# cc2520_cc2592.net
KiCad netlist of a schematic drawn in Altium Designer
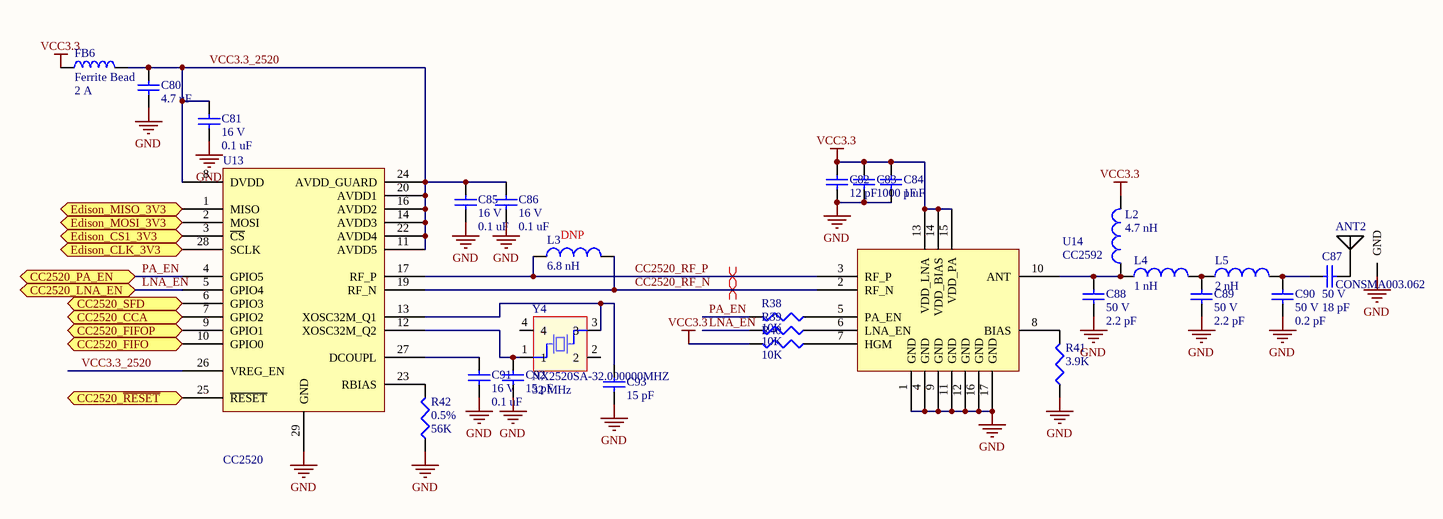
[diagram p0: cc2520_cc2592.SchDoc]

(export (version "E")
  (design (tool "Eeschema 10.0.6"))
  (components
    (comp (ref "ANT2")
      (value "CONSMA003.062")
      (footprint "CONSMA003.062")
      (description "CONN SMA JACK 50 OHM EDGE MNT")
      (libsource (lib "RF") (part "CONSMA003.062"))
    )
    (comp (ref "C80")
      (value "4.7 uF")
      (footprint "0603")
      (description "Ceramic capacitor, 4.7u, 10V, 0603 package")
      (fields (field (name "TOLERANCE") "20%") (field (name "Comment") "Ceramic capacitor"))
      (libsource (lib "rlc") (part "C_4.7u_10V_0603_ceramic"))
    )
    (comp (ref "C81")
      (value "0.1 uF")
      (footprint "0402")
      (description "Ceramic capacitor, 0.1u, 16 V, 0402 package")
      (fields
        (field (name "TOLERANCE") "10%")
        (field (name "VOLTAGE RATED") "16 V")
        (field (name "Comment") "Ceramic capacitor")
      )
      (libsource (lib "rlc") (part "C_0.1u_16V_0402_ceramic"))
    )
    (comp (ref "C82")
      (value "12 pF")
      (footprint "0402")
      (description "Ceramic capacitor, 12 pF, 0402 package")
      (fields (field (name "TOLERANCE") "2%") (field (name "Comment") "Ceramic capacitor"))
      (libsource (lib "rlc") (part "C_12p_0402_ceramic"))
    )
    (comp (ref "C83")
      (value "1000 pF")
      (footprint "0402")
      (description "Ceramic capacitor, 1000 pF, 0402 package")
      (fields (field (name "TOLERANCE") "10%") (field (name "Comment") "Ceramic capacitor"))
      (libsource (lib "rlc") (part "C_1000p_50V_0402_ceramic"))
    )
    (comp (ref "C84")
      (value "1 uF")
      (footprint "0402")
      (description "Ceramic capacitor, 1 uF, 16V, 0402 package")
      (fields (field (name "TOLERANCE") "10%") (field (name "Comment") "Ceramic capacitor"))
      (libsource (lib "rlc") (part "C_1u_16V_0402_ceramic"))
    )
    (comp (ref "C85")
      (value "0.1 uF")
      (footprint "0402")
      (description "Ceramic capacitor, 0.1u, 16 V, 0402 package")
      (fields
        (field (name "TOLERANCE") "10%")
        (field (name "VOLTAGE RATED") "16 V")
        (field (name "Comment") "Ceramic capacitor")
      )
      (libsource (lib "rlc") (part "C_0.1u_16V_0402_ceramic"))
    )
    (comp (ref "C86")
      (value "0.1 uF")
      (footprint "0402")
      (description "Ceramic capacitor, 0.1u, 16 V, 0402 package")
      (fields
        (field (name "TOLERANCE") "10%")
        (field (name "VOLTAGE RATED") "16 V")
        (field (name "Comment") "Ceramic capacitor")
      )
      (libsource (lib "rlc") (part "C_0.1u_16V_0402_ceramic"))
    )
    (comp (ref "C87")
      (value "18 pF")
      (footprint "0402")
      (description "Ceramic capacitor, 18 pF, 0402 package")
      (fields
        (field (name "TOLERANCE") "2%")
        (field (name "VOLTAGE RATED") "50 V")
        (field (name "Comment") "Ceramic capacitor")
      )
      (libsource (lib "rlc") (part "C_18p_50V_0402_ceramic"))
    )
    (comp (ref "C88")
      (value "2.2 pF")
      (footprint "0402")
      (description "Ceramic capacitor, 2.2 pF, 0402 package")
      (fields
        (field (name "TOLERANCE") "0.1 pF")
        (field (name "VOLTAGE RATED") "50 V")
        (field (name "Comment") "Ceramic capacitor")
      )
      (libsource (lib "rlc") (part "C_2.2p_50V_0402_ceramic"))
    )
    (comp (ref "C89")
      (value "2.2 pF")
      (footprint "0402")
      (description "Ceramic capacitor, 2.2 pF, 0402 package")
      (fields
        (field (name "TOLERANCE") "0.1 pF")
        (field (name "VOLTAGE RATED") "50 V")
        (field (name "Comment") "Ceramic capacitor")
      )
      (libsource (lib "rlc") (part "C_2.2p_50V_0402_ceramic"))
    )
    (comp (ref "C90")
      (value "0.2 pF")
      (footprint "0402")
      (description "Ceramic capacitor, 0.2 pF, 0402 package")
      (fields
        (field (name "TOLERANCE") "0.05 pF")
        (field (name "VOLTAGE RATED") "50 V")
        (field (name "Comment") "Ceramic capacitor")
      )
      (libsource (lib "rlc") (part "C_0.2p_50V_0402_ceramic"))
    )
    (comp (ref "C91")
      (value "0.1 uF")
      (footprint "0402")
      (description "Ceramic capacitor, 0.1u, 16 V, 0402 package")
      (fields
        (field (name "TOLERANCE") "10%")
        (field (name "VOLTAGE RATED") "16 V")
        (field (name "Comment") "Ceramic capacitor")
      )
      (libsource (lib "rlc") (part "C_0.1u_16V_0402_ceramic"))
    )
    (comp (ref "C92")
      (value "15 pF")
      (footprint "0402")
      (description "Ceramic capacitor, 15 pF, 25V, 0402 package")
      (fields (field (name "TOLERANCE") "5%") (field (name "Comment") "Ceramic capacitor"))
      (libsource (lib "rlc") (part "C_15p_25V_0402_ceramic"))
    )
    (comp (ref "C93")
      (value "15 pF")
      (footprint "0402")
      (description "Ceramic capacitor, 15 pF, 25V, 0402 package")
      (fields (field (name "TOLERANCE") "5%") (field (name "Comment") "Ceramic capacitor"))
      (libsource (lib "rlc") (part "C_15p_25V_0402_ceramic"))
    )
    (comp (ref "FB6")
      (value "Ferrite Bead")
      (footprint "0603")
      (description "Ferrite Bead, 2 A, 0603 package")
      (fields (field (name "CURRENT RATING") "2 A"))
      (libsource (lib "rlc") (part "FB_2A_0603"))
    )
    (comp (ref "L2")
      (value "4.7 nH")
      (footprint "0402")
      (description "Chip inductor, 4.7 nH, 0402 package, 300 mA")
      (fields (field (name "TOLERANCE") "0.3 nH") (field (name "Comment") "Chip inductor"))
      (libsource (lib "rlc") (part "L_4.7n_300mA_0402"))
    )
    (comp (ref "L3")
      (value "6.8 nH")
      (footprint "0402")
      (description "Chip inductor, 6.8 nH, 0402 package")
      (fields (field (name "TOLERANCE") "5%") (field (name "Comment") "Chip inductor"))
      (libsource (lib "rlc") (part "L_6.8n_0402"))
    )
    (comp (ref "L4")
      (value "1 nH")
      (footprint "0402")
      (description "Chip inductor, 1 nH, 0402 package, 300 mA")
      (fields (field (name "TOLERANCE") "0.3 nH") (field (name "Comment") "Chip inductor"))
      (libsource (lib "rlc") (part "L_1n_300mA_0402"))
    )
    (comp (ref "L5")
      (value "2 nH")
      (footprint "0402")
      (description "Chip inductor, 2 nH, 0402 package, 300 mA")
      (fields (field (name "TOLERANCE") "0.3 nH") (field (name "Comment") "Chip inductor"))
      (libsource (lib "rlc") (part "L_2n_300mA_0402"))
    )
    (comp (ref "R38")
      (value "10K")
      (footprint "0402")
      (description "Chip resistor, 10K, 0402 package")
      (fields (field (name "TOLERANCE") "1%") (field (name "POWER") "1/16 W"))
      (libsource (lib "rlc") (part "R_10K_0402"))
    )
    (comp (ref "R39")
      (value "10K")
      (footprint "0402")
      (description "Chip resistor, 10K, 0402 package")
      (fields (field (name "TOLERANCE") "1%") (field (name "POWER") "1/16 W"))
      (libsource (lib "rlc") (part "R_10K_0402"))
    )
    (comp (ref "R40")
      (value "10K")
      (footprint "0402")
      (description "Chip resistor, 10K, 0402 package")
      (fields (field (name "TOLERANCE") "1%") (field (name "POWER") "1/16 W"))
      (libsource (lib "rlc") (part "R_10K_0402"))
    )
    (comp (ref "R41")
      (value "3.9K")
      (footprint "0402")
      (description "Chip resistor, 3.9K, 0402 package")
      (fields (field (name "TOLERANCE") "1%") (field (name "POWER") "1/16 W"))
      (libsource (lib "rlc") (part "R_3.9K_0402"))
    )
    (comp (ref "R42")
      (value "56K")
      (footprint "0402")
      (description "Chip resistor, 56K, 0402 package")
      (fields
        (field (name "POWER") "1/16 W")
        (field (name "TOLERANCE") "0.5%")
        (field (name "Comment") "Chip resistor")
      )
      (libsource (lib "rlc") (part "R_56K_0402"))
    )
    (comp (ref "U13")
      (value "CC2520")
      (footprint "QFN-28")
      (description "2.4 GHZ IEEE 802.15.4/ZIGBEE® RF TRANSCEIVER")
      (libsource (lib "RF") (part "CC2520"))
    )
    (comp (ref "U14")
      (value "CC2592")
      (footprint "QFN-16")
      (description "2.4-GHz Range Extender")
      (libsource (lib "RF") (part "CC2592"))
    )
    (comp (ref "Y4")
      (value "NX2520SA-32.000000MHZ")
      (footprint "NX2520SA")
      (description "Crystal 32.0000MHz 10ppm 10pF 50 Ohm")
      (fields (field (name "FREQUENCY") "32 MHz"))
      (libsource (lib "crystal_oscillators_rtc") (part "NX2520SA-32.000000MHZ"))
    )
  )
  (nets
    (net (code "1") (name "/CC2520_CCA") (class "Default")
      (node (ref "U13") (pin "7") (pinfunction "GPIO2_7") (pintype "passive"))
    )
    (net (code "2") (name "/CC2520_FIFO") (class "Default")
      (node (ref "U13") (pin "10") (pinfunction "GPIO0_10") (pintype "passive"))
    )
    (net (code "3") (name "/CC2520_FIFOP") (class "Default")
      (node (ref "U13") (pin "9") (pinfunction "GPIO1_9") (pintype "passive"))
    )
    (net (code "4") (name "/CC2520_RF_N") (class "Default")
      (node (ref "L3") (pin "1") (pintype "passive"))
      (node (ref "U13") (pin "19") (pinfunction "RF_N_19") (pintype "passive"))
      (node (ref "U14") (pin "2") (pinfunction "RF_N_2") (pintype "passive"))
    )
    (net (code "5") (name "/CC2520_RF_P") (class "Default")
      (node (ref "L3") (pin "2") (pintype "passive"))
      (node (ref "U13") (pin "17") (pinfunction "RF_P_17") (pintype "passive"))
      (node (ref "U14") (pin "3") (pinfunction "RF_P_3") (pintype "passive"))
    )
    (net (code "6") (name "/CC2520_SFD") (class "Default")
      (node (ref "U13") (pin "6") (pinfunction "GPIO3_6") (pintype "passive"))
    )
    (net (code "7") (name "/CC2520_~{RESET}") (class "Default")
      (node (ref "U13") (pin "25") (pinfunction "~{RESET}_25") (pintype "passive"))
    )
    (net (code "8") (name "/Edison_CLK_3V3") (class "Default")
      (node (ref "U13") (pin "28") (pinfunction "SCLK_28") (pintype "passive"))
    )
    (net (code "9") (name "/Edison_CS1_3V3") (class "Default")
      (node (ref "U13") (pin "3") (pinfunction "~{CS}_3") (pintype "passive"))
    )
    (net (code "10") (name "/Edison_MISO_3V3") (class "Default")
      (node (ref "U13") (pin "1") (pinfunction "MISO_1") (pintype "passive"))
    )
    (net (code "11") (name "/Edison_MOSI_3V3") (class "Default")
      (node (ref "U13") (pin "2") (pinfunction "MOSI_2") (pintype "passive"))
    )
    (net (code "12") (name "/LNA_EN") (class "Default")
      (node (ref "R39") (pin "1") (pintype "passive"))
      (node (ref "U13") (pin "5") (pinfunction "GPIO4_5") (pintype "passive"))
    )
    (net (code "13") (name "/PA_EN") (class "Default")
      (node (ref "R38") (pin "1") (pintype "passive"))
      (node (ref "U13") (pin "4") (pinfunction "GPIO5_4") (pintype "passive"))
    )
    (net (code "14") (name "/VCC3.3_2520") (class "Default")
      (node (ref "C80") (pin "1") (pintype "passive"))
      (node (ref "C81") (pin "1") (pintype "passive"))
      (node (ref "C85") (pin "1") (pintype "passive"))
      (node (ref "C86") (pin "1") (pintype "passive"))
      (node (ref "FB6") (pin "1") (pintype "passive"))
      (node (ref "U13") (pin "11") (pinfunction "AVDD5_11") (pintype "passive"))
      (node (ref "U13") (pin "14") (pinfunction "AVDD3_14") (pintype "passive"))
      (node (ref "U13") (pin "16") (pinfunction "AVDD2_16") (pintype "passive"))
      (node (ref "U13") (pin "20") (pinfunction "AVDD1_20") (pintype "passive"))
      (node (ref "U13") (pin "22") (pinfunction "AVDD4_22") (pintype "passive"))
      (node (ref "U13") (pin "24") (pinfunction "AVDD_GUARD_24") (pintype "passive"))
      (node (ref "U13") (pin "26") (pinfunction "VREG_EN_26") (pintype "passive"))
      (node (ref "U13") (pin "8") (pinfunction "DVDD_8") (pintype "passive"))
    )
    (net (code "15") (name "GND") (class "Default")
      (node (ref "ANT2") (pin "1") (pinfunction "GND_1") (pintype "power_in"))
      (node (ref "C80") (pin "2") (pintype "passive"))
      (node (ref "C81") (pin "2") (pintype "passive"))
      (node (ref "C82") (pin "2") (pintype "passive"))
      (node (ref "C83") (pin "2") (pintype "passive"))
      (node (ref "C84") (pin "2") (pintype "passive"))
      (node (ref "C85") (pin "2") (pintype "passive"))
      (node (ref "C86") (pin "2") (pintype "passive"))
      (node (ref "C88") (pin "2") (pintype "passive"))
      (node (ref "C89") (pin "2") (pintype "passive"))
      (node (ref "C90") (pin "2") (pintype "passive"))
      (node (ref "C91") (pin "2") (pintype "passive"))
      (node (ref "C92") (pin "2") (pintype "passive"))
      (node (ref "C93") (pin "2") (pintype "passive"))
      (node (ref "R41") (pin "2") (pintype "passive"))
      (node (ref "R42") (pin "2") (pintype "passive"))
      (node (ref "U13") (pin "29") (pinfunction "GND_29") (pintype "passive"))
      (node (ref "U14") (pin "1") (pinfunction "GND_1") (pintype "passive"))
      (node (ref "U14") (pin "11") (pinfunction "GND_11") (pintype "passive"))
      (node (ref "U14") (pin "12") (pinfunction "GND_12") (pintype "passive"))
      (node (ref "U14") (pin "16") (pinfunction "GND_16") (pintype "passive"))
      (node (ref "U14") (pin "17") (pinfunction "GND_17") (pintype "passive"))
      (node (ref "U14") (pin "4") (pinfunction "GND_4") (pintype "passive"))
      (node (ref "U14") (pin "9") (pinfunction "GND_9") (pintype "passive"))
    )
    (net (code "16") (name "Net-(ANT2-Pad2)") (class "Default")
      (node (ref "ANT2") (pin "2") (pintype "passive"))
      (node (ref "C87") (pin "2") (pintype "passive"))
    )
    (net (code "17") (name "Net-(C87-Pad1)") (class "Default")
      (node (ref "C87") (pin "1") (pintype "passive"))
      (node (ref "C90") (pin "1") (pintype "passive"))
      (node (ref "L5") (pin "1") (pintype "passive"))
    )
    (net (code "18") (name "Net-(C89-Pad1)") (class "Default")
      (node (ref "C89") (pin "1") (pintype "passive"))
      (node (ref "L4") (pin "1") (pintype "passive"))
      (node (ref "L5") (pin "2") (pintype "passive"))
    )
    (net (code "19") (name "Net-(U13-DCOUPL)") (class "Default")
      (node (ref "C91") (pin "1") (pintype "passive"))
      (node (ref "U13") (pin "27") (pinfunction "DCOUPL_27") (pintype "passive"))
    )
    (net (code "20") (name "Net-(U13-RBIAS)") (class "Default")
      (node (ref "R42") (pin "1") (pintype "passive"))
      (node (ref "U13") (pin "23") (pinfunction "RBIAS_23") (pintype "passive"))
    )
    (net (code "21") (name "Net-(U13-XOSC32M_Q1)") (class "Default")
      (node (ref "C93") (pin "1") (pintype "passive"))
      (node (ref "U13") (pin "13") (pinfunction "XOSC32M_Q1_13") (pintype "passive"))
      (node (ref "Y4") (pin "3") (pinfunction "3_3") (pintype "passive"))
    )
    (net (code "22") (name "Net-(U13-XOSC32M_Q2)") (class "Default")
      (node (ref "C92") (pin "1") (pintype "passive"))
      (node (ref "U13") (pin "12") (pinfunction "XOSC32M_Q2_12") (pintype "passive"))
      (node (ref "Y4") (pin "1") (pinfunction "1_1") (pintype "passive"))
    )
    (net (code "23") (name "Net-(U14-ANT)") (class "Default")
      (node (ref "C88") (pin "1") (pintype "passive"))
      (node (ref "L2") (pin "2") (pintype "passive"))
      (node (ref "L4") (pin "2") (pintype "passive"))
      (node (ref "U14") (pin "10") (pinfunction "ANT_10") (pintype "passive"))
    )
    (net (code "24") (name "Net-(U14-BIAS)") (class "Default")
      (node (ref "R41") (pin "1") (pintype "passive"))
      (node (ref "U14") (pin "8") (pinfunction "BIAS_8") (pintype "passive"))
    )
    (net (code "25") (name "Net-(U14-HGM)") (class "Default")
      (node (ref "R40") (pin "2") (pintype "passive"))
      (node (ref "U14") (pin "7") (pinfunction "HGM_7") (pintype "passive"))
    )
    (net (code "26") (name "Net-(U14-LNA_EN)") (class "Default")
      (node (ref "R39") (pin "2") (pintype "passive"))
      (node (ref "U14") (pin "6") (pinfunction "LNA_EN_6") (pintype "passive"))
    )
    (net (code "27") (name "Net-(U14-PA_EN)") (class "Default")
      (node (ref "R38") (pin "2") (pintype "passive"))
      (node (ref "U14") (pin "5") (pinfunction "PA_EN_5") (pintype "passive"))
    )
    (net (code "28") (name "VCC3.3") (class "Default")
      (node (ref "C82") (pin "1") (pintype "passive"))
      (node (ref "C83") (pin "1") (pintype "passive"))
      (node (ref "C84") (pin "1") (pintype "passive"))
      (node (ref "FB6") (pin "2") (pintype "passive"))
      (node (ref "L2") (pin "1") (pintype "passive"))
      (node (ref "R40") (pin "1") (pintype "passive"))
      (node (ref "U14") (pin "13") (pinfunction "VDD_LNA_13") (pintype "passive"))
      (node (ref "U14") (pin "14") (pinfunction "VDD_BIAS_14") (pintype "passive"))
      (node (ref "U14") (pin "15") (pinfunction "VDD_PA_15") (pintype "passive"))
    )
    (net (code "29") (name "unconnected-(Y4-Pad2)") (class "Default")
      (node (ref "Y4") (pin "2") (pinfunction "2_2") (pintype "passive"))
    )
    (net (code "30") (name "unconnected-(Y4-Pad4)") (class "Default")
      (node (ref "Y4") (pin "4") (pinfunction "4_4") (pintype "passive"))
    )
  )
)
